# lipo-charge-reg-protect.net
KiCad netlist of a schematic drawn in EAGLE
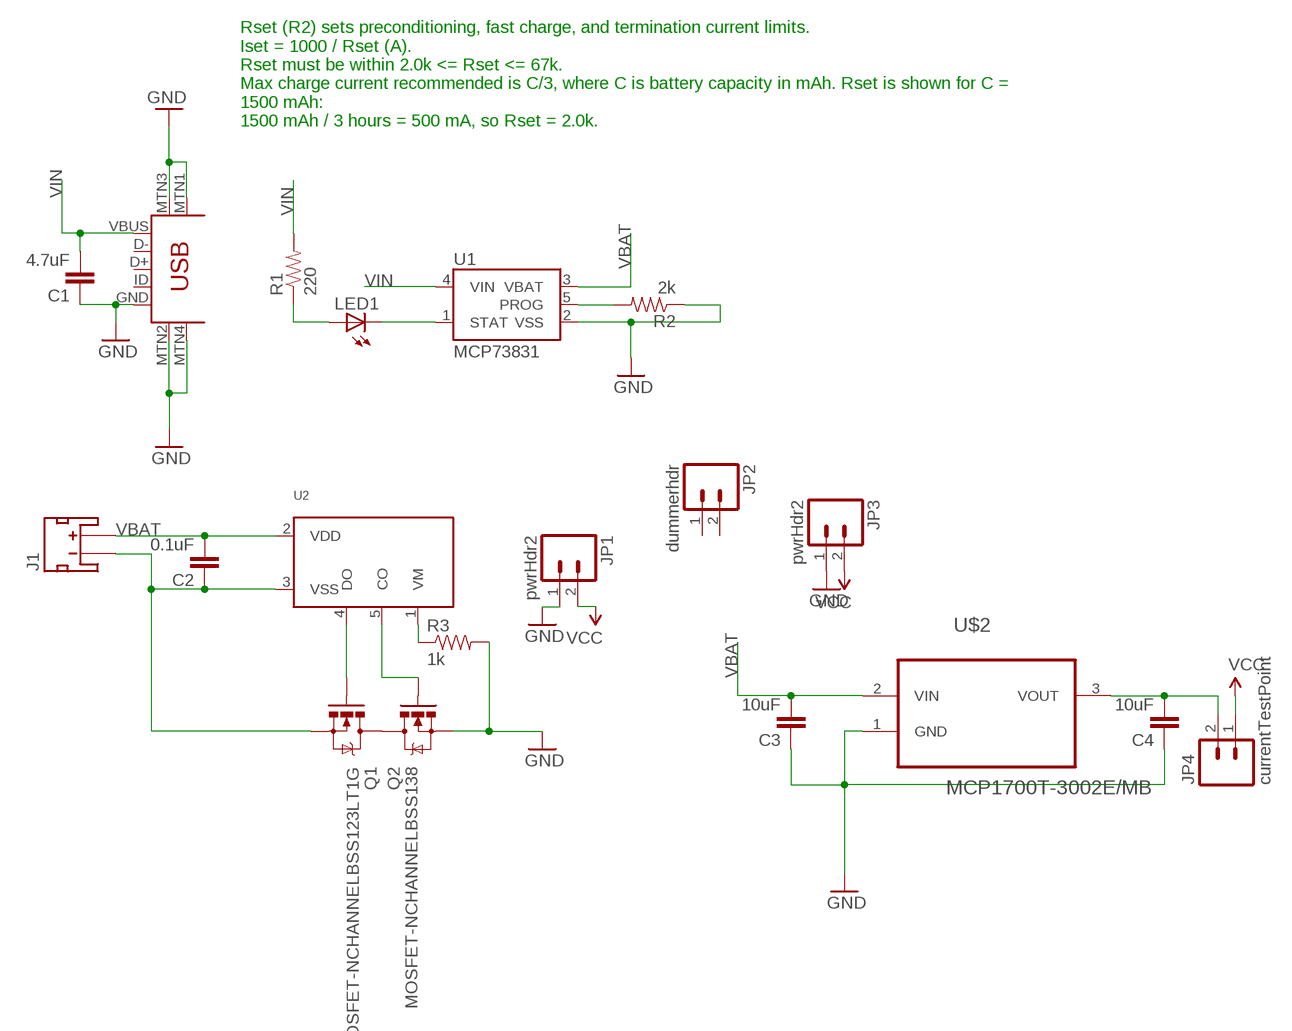
[diagram p0: schematic, sheet 1]

(export (version "E")
  (design (tool "Eeschema 10.0.6"))
  (components
    (comp (ref "C1")
      (value "4.7uF")
      (footprint "eagle-import:0603-CAP")
      (libsource (lib "eagle-import") (part "0.1UF-25V(+80/-20%)(0603)"))
    )
    (comp (ref "C2")
      (value "0.1uF")
      (footprint "eagle-import:0603-CAP")
      (libsource (lib "eagle-import") (part "0.1UF-25V(+80/-20%)(0603)"))
    )
    (comp (ref "C3")
      (value "10uF")
      (footprint "eagle-import:0603-CAP")
      (libsource (lib "eagle-import") (part "0.1UF-25V(+80/-20%)(0603)"))
    )
    (comp (ref "C4")
      (value "10uF")
      (footprint "eagle-import:0603-CAP")
      (libsource (lib "eagle-import") (part "0.1UF-25V(+80/-20%)(0603)"))
    )
    (comp (ref "J1")
      (value "JST_2MM_MALE")
      (footprint "eagle-import:JST-2-SMD")
      (libsource (lib "eagle-import") (part "JST_2MM_MALE"))
    )
    (comp (ref "JP1")
      (value "pwrHdr2")
      (footprint "eagle-import:1X02_LOCK_LONGPADS")
      (libsource (lib "eagle-import") (part "M02LOCK_LONGPADS"))
    )
    (comp (ref "JP2")
      (value "dummerhdr")
      (footprint "eagle-import:1X02_LOCK_LONGPADS")
      (libsource (lib "eagle-import") (part "M02LOCK_LONGPADS"))
    )
    (comp (ref "JP3")
      (value "pwrHdr2")
      (footprint "eagle-import:1X02_LOCK_LONGPADS")
      (libsource (lib "eagle-import") (part "M02LOCK_LONGPADS"))
    )
    (comp (ref "JP4")
      (value "currentTestPoint")
      (footprint "eagle-import:1X02_LOCK_LONGPADS")
      (libsource (lib "eagle-import") (part "M02LOCK_LONGPADS"))
    )
    (comp (ref "LED1")
      (value "LED0603")
      (footprint "eagle-import:LED-0603")
      (libsource (lib "eagle-import") (part "LED0603"))
    )
    (comp (ref "Q1")
      (value "MOSFET-NCHANNELBSS123LT1G")
      (footprint "eagle-import:SOT23")
      (libsource (lib "eagle-import") (part "MOSFET-NCHANNELBSS123LT1G"))
    )
    (comp (ref "Q2")
      (value "MOSFET-NCHANNELBSS138")
      (footprint "eagle-import:SOT23")
      (libsource (lib "eagle-import") (part "MOSFET-NCHANNELBSS138"))
    )
    (comp (ref "R1")
      (value "220")
      (footprint "eagle-import:0603")
      (libsource (lib "eagle-import") (part "0OHM1/10W5%(0603)"))
    )
    (comp (ref "R2")
      (value "2k")
      (footprint "eagle-import:0603")
      (libsource (lib "eagle-import") (part "0OHM1/10W5%(0603)"))
    )
    (comp (ref "R3")
      (value "1k")
      (footprint "eagle-import:0603")
      (libsource (lib "eagle-import") (part "0OHM1/10W5%(0603)"))
    )
    (comp (ref "U$1")
      (value "USB-MINIB-5PIN")
      (footprint "eagle-import:USB-MINIB")
      (libsource (lib "eagle-import") (part "USB-MINIB-5PIN"))
    )
    (comp (ref "U$2")
      (value "MCP1700T-3002E/MB")
      (footprint "eagle-import:SOT89")
      (libsource (lib "eagle-import") (part "MCP1700T-3002E/MB"))
    )
    (comp (ref "U1")
      (value "MCP73831")
      (footprint "eagle-import:SOT23-5")
      (libsource (lib "eagle-import") (part "MCP73831"))
    )
    (comp (ref "U2")
      (value "S-8241")
      (footprint "eagle-import:SOT23-5L")
      (libsource (lib "eagle-import") (part "S-8241"))
    )
  )
  (nets
    (net (code "1") (name "/VBAT") (class "Default")
      (node (ref "C2") (pin "2") (pinfunction "2_2") (pintype "passive"))
      (node (ref "C3") (pin "2") (pinfunction "2_2") (pintype "passive"))
      (node (ref "J1") (pin "2") (pinfunction "+_2") (pintype "bidirectional"))
      (node (ref "U$2") (pin "2") (pinfunction "VIN_2") (pintype "input"))
      (node (ref "U1") (pin "3") (pinfunction "VBAT_3") (pintype "power_in"))
      (node (ref "U2") (pin "2") (pinfunction "VDD_2") (pintype "power_in"))
    )
    (net (code "2") (name "/VIN") (class "Default")
      (node (ref "C1") (pin "2") (pinfunction "2_2") (pintype "passive"))
      (node (ref "R1") (pin "2") (pinfunction "2_2") (pintype "passive"))
      (node (ref "U$1") (pin "VBUS") (pinfunction "VBUS_VBUS") (pintype "bidirectional"))
      (node (ref "U1") (pin "4") (pinfunction "VIN_4") (pintype "power_in"))
    )
    (net (code "3") (name "GND") (class "Default")
      (node (ref "C1") (pin "1") (pinfunction "1_1") (pintype "passive"))
      (node (ref "C3") (pin "1") (pinfunction "1_1") (pintype "passive"))
      (node (ref "C4") (pin "1") (pinfunction "1_1") (pintype "passive"))
      (node (ref "JP1") (pin "1") (pinfunction "1_1") (pintype "passive"))
      (node (ref "JP3") (pin "1") (pinfunction "1_1") (pintype "passive"))
      (node (ref "Q2") (pin "2") (pinfunction "S_2") (pintype "passive"))
      (node (ref "R2") (pin "1") (pinfunction "1_1") (pintype "passive"))
      (node (ref "R3") (pin "2") (pinfunction "2_2") (pintype "passive"))
      (node (ref "U$1") (pin "GND") (pinfunction "GND_GND") (pintype "bidirectional"))
      (node (ref "U$1") (pin "MTN1") (pinfunction "MTN2_MTN1") (pintype "bidirectional"))
      (node (ref "U$1") (pin "MTN2") (pinfunction "MTN3_MTN2") (pintype "bidirectional"))
      (node (ref "U$1") (pin "MTN3") (pinfunction "MTN1_MTN3") (pintype "bidirectional"))
      (node (ref "U$1") (pin "MTN4") (pinfunction "MTN4_MTN4") (pintype "bidirectional"))
      (node (ref "U$2") (pin "1") (pinfunction "GND_1") (pintype "passive"))
      (node (ref "U1") (pin "2") (pinfunction "VSS_2") (pintype "power_in"))
    )
    (net (code "4") (name "Net-(J1--)") (class "Default")
      (node (ref "C2") (pin "1") (pinfunction "1_1") (pintype "passive"))
      (node (ref "J1") (pin "1") (pinfunction "-_1") (pintype "bidirectional"))
      (node (ref "Q1") (pin "2") (pinfunction "S_2") (pintype "passive"))
      (node (ref "U2") (pin "3") (pinfunction "VSS_3") (pintype "power_in"))
    )
    (net (code "5") (name "Net-(LED1-PadA)") (class "Default")
      (node (ref "LED1") (pin "A") (pinfunction "A_A") (pintype "passive"))
      (node (ref "R1") (pin "1") (pinfunction "1_1") (pintype "passive"))
    )
    (net (code "6") (name "Net-(Q1-D)") (class "Default")
      (node (ref "Q1") (pin "3") (pinfunction "D_3") (pintype "passive"))
      (node (ref "Q2") (pin "3") (pinfunction "D_3") (pintype "passive"))
    )
    (net (code "7") (name "Net-(Q1-G)") (class "Default")
      (node (ref "Q1") (pin "1") (pinfunction "G_1") (pintype "passive"))
      (node (ref "U2") (pin "4") (pinfunction "DO_4") (pintype "power_in"))
    )
    (net (code "8") (name "Net-(Q2-G)") (class "Default")
      (node (ref "Q2") (pin "1") (pinfunction "G_1") (pintype "passive"))
      (node (ref "U2") (pin "5") (pinfunction "CO_5") (pintype "bidirectional"))
    )
    (net (code "9") (name "Net-(U$2-VOUT)") (class "Default")
      (node (ref "C4") (pin "2") (pinfunction "2_2") (pintype "passive"))
      (node (ref "JP4") (pin "2") (pinfunction "2_2") (pintype "passive"))
      (node (ref "U$2") (pin "3") (pinfunction "VOUT_3") (pintype "output"))
    )
    (net (code "10") (name "Net-(U1-PROG)") (class "Default")
      (node (ref "R2") (pin "2") (pinfunction "2_2") (pintype "passive"))
      (node (ref "U1") (pin "5") (pinfunction "PROG_5") (pintype "input"))
    )
    (net (code "11") (name "Net-(U1-STAT)") (class "Default")
      (node (ref "LED1") (pin "C") (pinfunction "C_C") (pintype "passive"))
      (node (ref "U1") (pin "1") (pinfunction "STAT_1") (pintype "output"))
    )
    (net (code "12") (name "Net-(U2-VM)") (class "Default")
      (node (ref "R3") (pin "1") (pinfunction "1_1") (pintype "passive"))
      (node (ref "U2") (pin "1") (pinfunction "VM_1") (pintype "power_in"))
    )
    (net (code "13") (name "VCC") (class "Default")
      (node (ref "JP1") (pin "2") (pinfunction "2_2") (pintype "passive"))
      (node (ref "JP3") (pin "2") (pinfunction "2_2") (pintype "passive"))
      (node (ref "JP4") (pin "1") (pinfunction "1_1") (pintype "passive"))
    )
    (net (code "14") (name "unconnected-(J1-PAD1-PadNC1)") (class "Default")
      (node (ref "J1") (pin "NC1") (pinfunction "PAD1_NC1") (pintype "bidirectional"))
    )
    (net (code "15") (name "unconnected-(J1-PAD2-PadNC2)") (class "Default")
      (node (ref "J1") (pin "NC2") (pinfunction "PAD2_NC2") (pintype "bidirectional"))
    )
    (net (code "16") (name "unconnected-(JP2-Pad1)") (class "Default")
      (node (ref "JP2") (pin "1") (pinfunction "1_1") (pintype "passive"))
    )
    (net (code "17") (name "unconnected-(JP2-Pad2)") (class "Default")
      (node (ref "JP2") (pin "2") (pinfunction "2_2") (pintype "passive"))
    )
    (net (code "18") (name "unconnected-(U$1-PadD+)") (class "Default")
      (node (ref "U$1") (pin "D+") (pinfunction "D+_D+") (pintype "bidirectional"))
    )
    (net (code "19") (name "unconnected-(U$1-PadD-)") (class "Default")
      (node (ref "U$1") (pin "D-") (pinfunction "D-_D-") (pintype "bidirectional"))
    )
    (net (code "20") (name "unconnected-(U$1-PadID)") (class "Default")
      (node (ref "U$1") (pin "ID") (pinfunction "ID_ID") (pintype "bidirectional"))
    )
  )
)
